# SCH_Camera-With-Light-Relay.net
KiCad netlist of a schematic drawn in EasyEDA
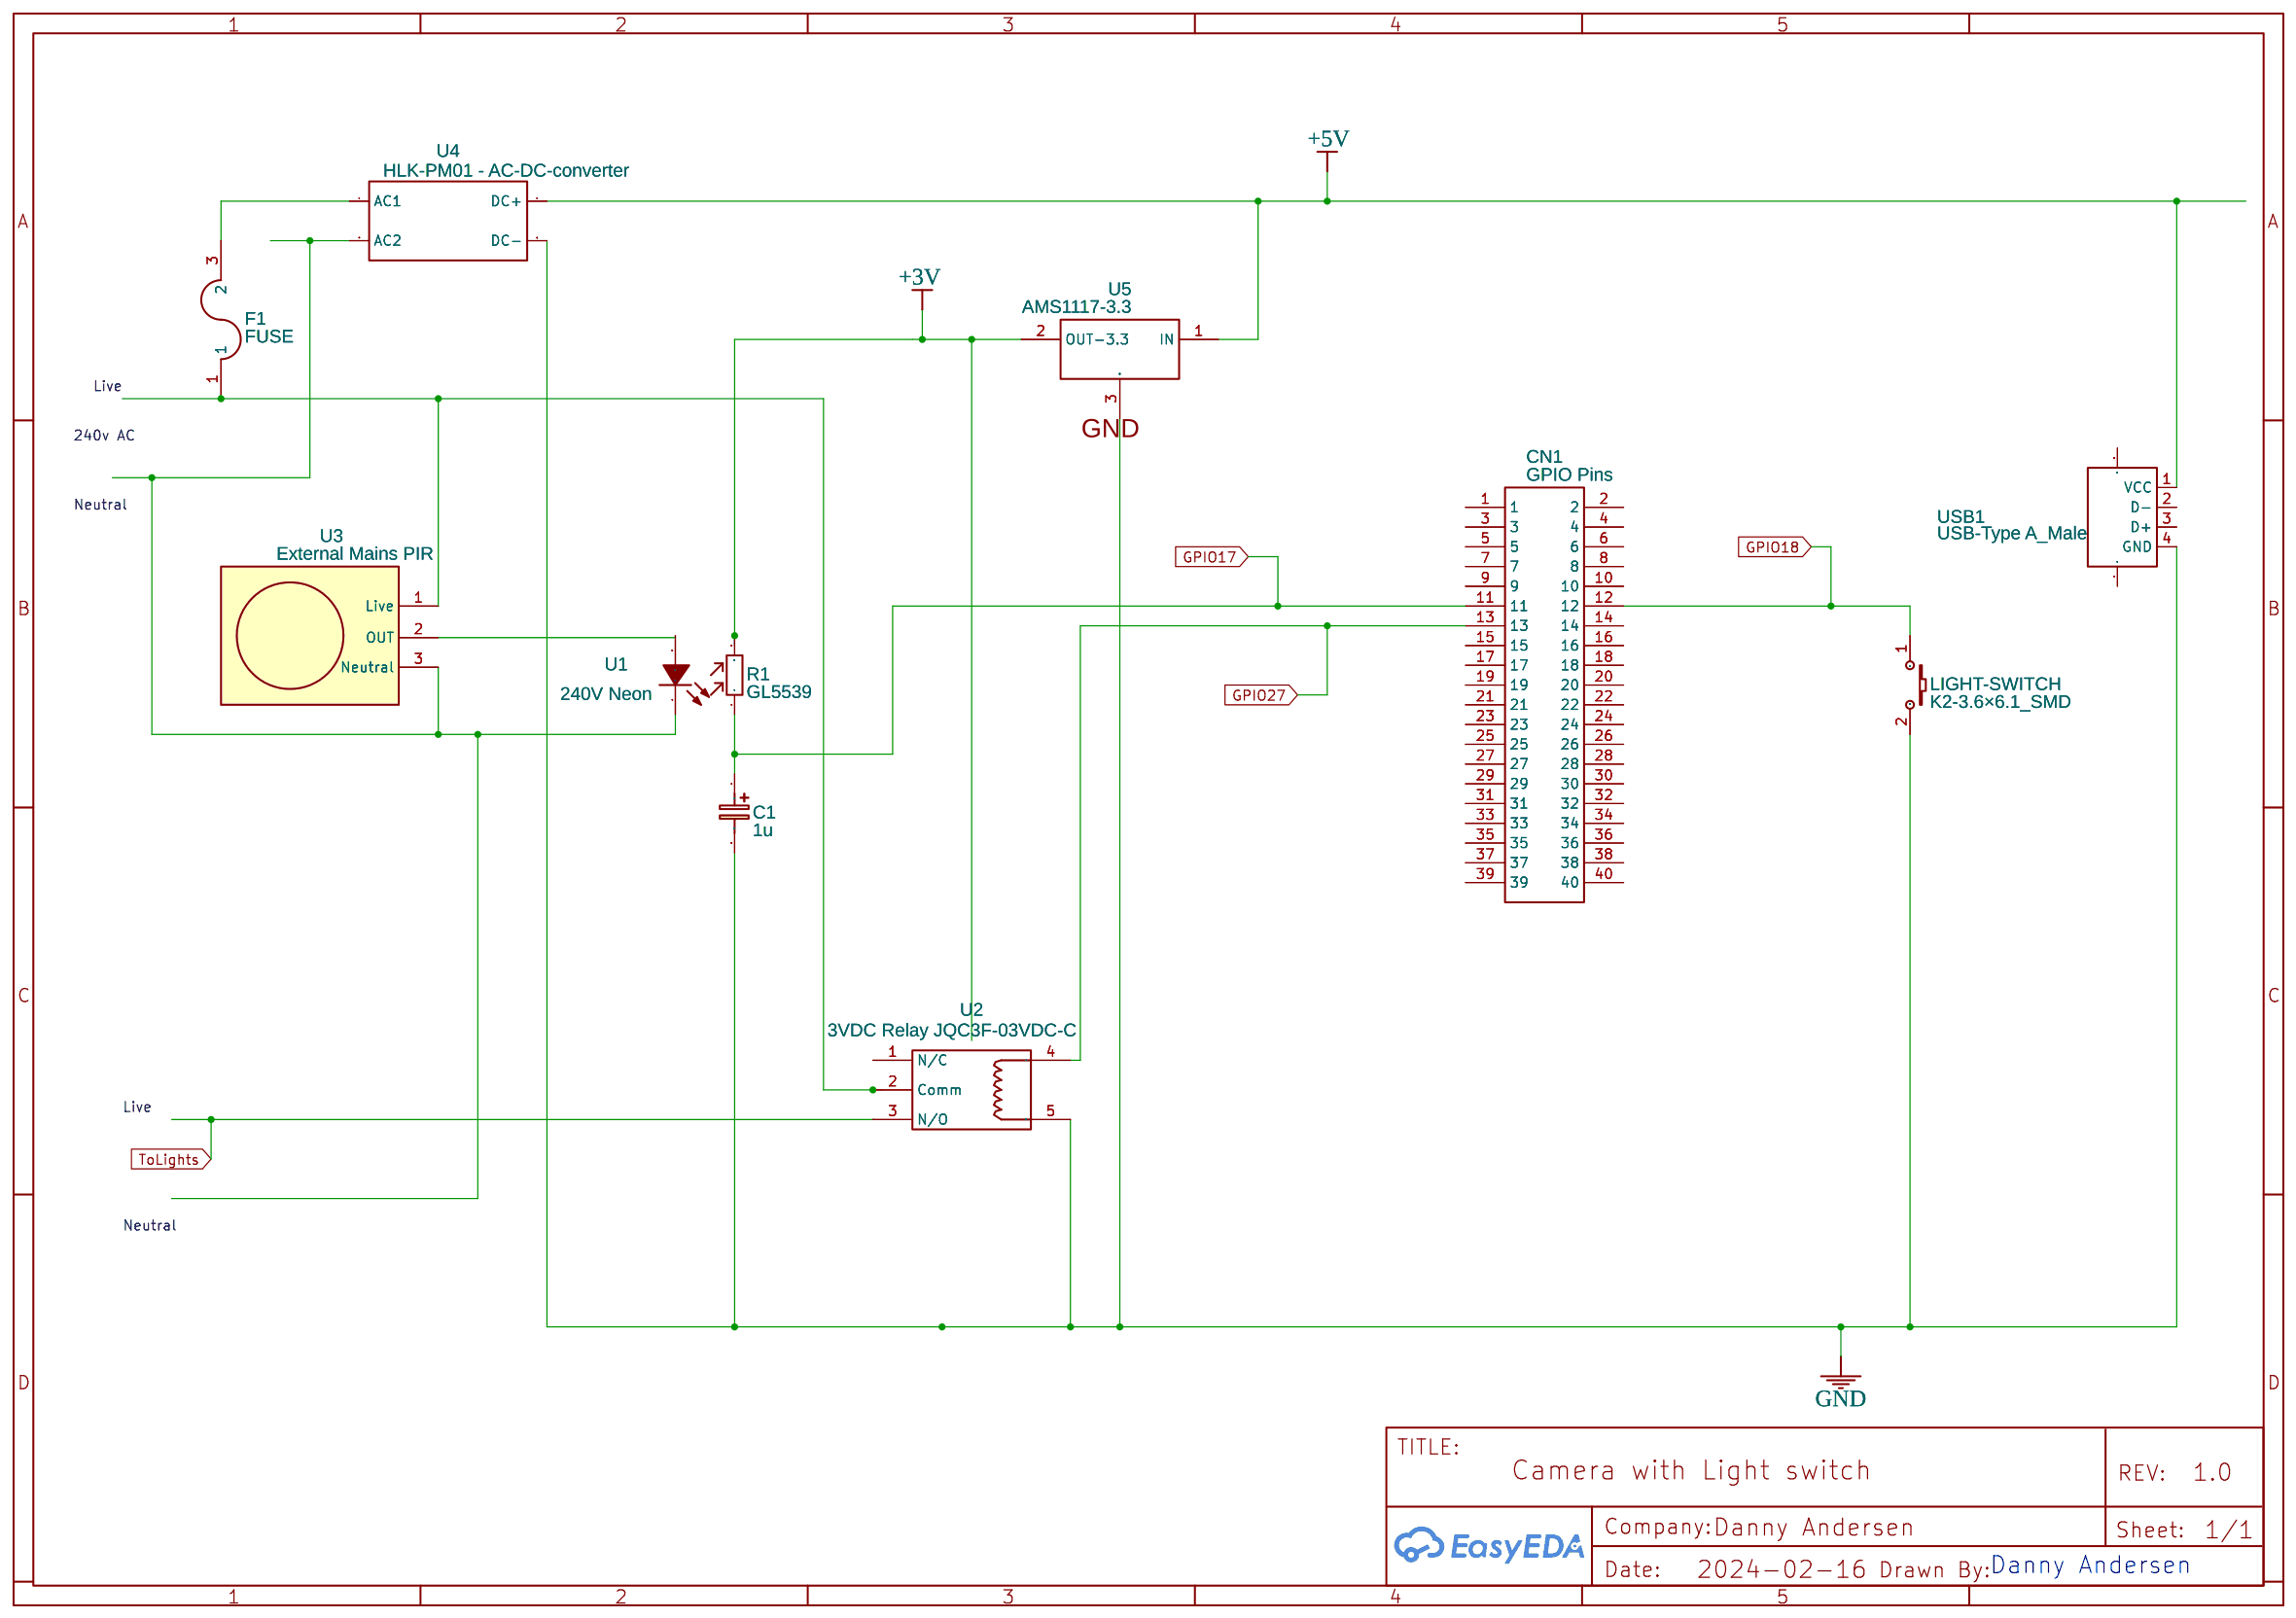
[diagram p0: schematic sheet]

(export (version "E")
  (design (tool "Eeschema 10.0.6"))
  (components
    (comp (ref "C1") (value "1u") (libsource (lib "") (part "C_Tan_SMD_A_EU")))
    (comp (ref "CN1")
      (value "GPIO Pins")
      (fields
        (field (name "Manufacturer Part") "2.54-2*20P压线头")
        (field (name "Manufacturer") "BOOMELE(博穆精密)")
      )
      (libsource (lib "") (part "Crimping terminals2*20"))
    )
    (comp (ref "F1")
      (value "FUSE")
      (fields (field (name "Manufacturer Part") "?"))
      (libsource (lib "") (part "Unknown_125_-1775"))
    )
    (comp (ref "LIGHT-SWITCH")
      (value "K2-3.6×6.1_SMD")
      (fields (field (name "Manufacturer Part") "K2-1107ST-A4SW-06"))
      (libsource (lib "") (part "K2-3.6×6.1_SMD"))
    )
    (comp (ref "R1")
      (value "GL5539")
      (fields (field (name "Manufacturer") "森霸"))
      (libsource (lib "") (part "GL5539"))
    )
    (comp (ref "U1")
      (value "240V Neon")
      (fields (field (name "Manufacturer Part") "720-LCGH9RNMXNX1"))
      (libsource (lib "") (part "720-LCGH9RNMXNX1"))
    )
    (comp (ref "U2")
      (value "3VDC Relay JQC3F-03VDC-C")
      (libsource (lib "") (part "3VDC Relay JQC3F-03VDC-C"))
    )
    (comp (ref "U3")
      (value "External Mains PIR")
      (fields (field (name "Manufacturer Part") "?"))
      (libsource (lib "") (part "Unknown_125_-1580"))
    )
    (comp (ref "U4")
      (value "HLK-PM01 - AC-DC-converter")
      (fields (field (name "Manufacturer Part") "?"))
      (libsource (lib "") (part "Unknown_230_-1825"))
    )
    (comp (ref "U5")
      (value "AMS1117-3.3")
      (fields (field (name "Manufacturer Part") "CJ78L05") (field (name "Manufacturer") "CJ"))
      (libsource (lib "") (part "7805(SOT-89)"))
    )
    (comp (ref "USB1")
      (value "USB-Type A_Male")
      (fields (field (name "Manufacturer Part") "USB-05") (field (name "Manufacturer") "SOFNG"))
      (libsource (lib "") (part "USB-Type A_Male"))
    )
  )
  (nets
    (net (code "1") (name "+3V") (class "Default")
      (node (ref "R1") (pin "2") (pinfunction "2_2") (pintype "input"))
      (node (ref "U5") (pin "2") (pinfunction "OUT-3.3_2") (pintype "passive"))
    )
    (net (code "2") (name "+5V") (class "Default")
      (node (ref "U4") (pin "4") (pinfunction "DC+_4") (pintype "unspecified"))
      (node (ref "U5") (pin "1") (pinfunction "IN_1") (pintype "passive"))
      (node (ref "USB1") (pin "1") (pinfunction "VCC_1") (pintype "input"))
    )
    (net (code "6") (name "GND") (class "Default")
      (node (ref "C1") (pin "2") (pinfunction "2_2") (pintype "unspecified"))
      (node (ref "LIGHT-SWITCH") (pin "2") (pinfunction "2_2") (pintype "unspecified"))
      (node (ref "U2") (pin "5") (pinfunction "5_5") (pintype "unspecified"))
      (node (ref "U4") (pin "3") (pinfunction "DC-_3") (pintype "unspecified"))
      (node (ref "U5") (pin "3") (pinfunction "GND_3") (pintype "passive"))
      (node (ref "USB1") (pin "4") (pinfunction "GND_4") (pintype "input"))
    )
    (net (code "7") (name "GPIO17") (class "Default")
      (node (ref "C1") (pin "1") (pinfunction "1_1") (pintype "unspecified"))
      (node (ref "CN1") (pin "11") (pinfunction "11_11") (pintype "unspecified"))
      (node (ref "R1") (pin "1") (pinfunction "1_1") (pintype "input"))
    )
    (net (code "8") (name "GPIO18") (class "Default")
      (node (ref "CN1") (pin "12") (pinfunction "12_12") (pintype "unspecified"))
      (node (ref "LIGHT-SWITCH") (pin "1") (pinfunction "1_1") (pintype "unspecified"))
    )
    (net (code "9") (name "GPIO27") (class "Default")
      (node (ref "CN1") (pin "13") (pinfunction "13_13") (pintype "unspecified"))
      (node (ref "U2") (pin "4") (pinfunction "4_4") (pintype "unspecified"))
    )
    (net (code "10") (name "Net-(F1-2)") (class "Default")
      (node (ref "F1") (pin "3") (pinfunction "2_3") (pintype "unspecified"))
      (node (ref "U4") (pin "1") (pinfunction "AC1_1") (pintype "input"))
    )
    (net (code "11") (name "Net-(U1-A)") (class "Default")
      (node (ref "U1") (pin "2") (pinfunction "A_2") (pintype "unspecified"))
      (node (ref "U3") (pin "2") (pinfunction "OUT_2") (pintype "unspecified"))
    )
    (net (code "12") (name "Net-(U1-K)") (class "Default")
      (node (ref "U1") (pin "1") (pinfunction "K_1") (pintype "unspecified"))
      (node (ref "U3") (pin "3") (pinfunction "Neutral_3") (pintype "unspecified"))
      (node (ref "U4") (pin "2") (pinfunction "AC2_2") (pintype "input"))
    )
    (net (code "13") (name "Net-(U2-Comm)") (class "Default")
      (node (ref "F1") (pin "1") (pinfunction "1_1") (pintype "unspecified"))
      (node (ref "U2") (pin "2") (pinfunction "Comm_2") (pintype "unspecified"))
      (node (ref "U3") (pin "1") (pinfunction "Live_1") (pintype "unspecified"))
    )
    (net (code "14") (name "ToLights") (class "Default")
      (node (ref "U2") (pin "3") (pinfunction "N/O_3") (pintype "unspecified"))
    )
    (net (code "15") (name "unconnected-(CN1-Pad1)") (class "Default")
      (node (ref "CN1") (pin "1") (pinfunction "1_1") (pintype "unspecified"))
    )
    (net (code "16") (name "unconnected-(CN1-Pad2)") (class "Default")
      (node (ref "CN1") (pin "2") (pinfunction "2_2") (pintype "unspecified"))
    )
    (net (code "17") (name "unconnected-(CN1-Pad3)") (class "Default")
      (node (ref "CN1") (pin "3") (pinfunction "3_3") (pintype "unspecified"))
    )
    (net (code "18") (name "unconnected-(CN1-Pad4)") (class "Default")
      (node (ref "CN1") (pin "4") (pinfunction "4_4") (pintype "unspecified"))
    )
    (net (code "19") (name "unconnected-(CN1-Pad5)") (class "Default")
      (node (ref "CN1") (pin "5") (pinfunction "5_5") (pintype "unspecified"))
    )
    (net (code "20") (name "unconnected-(CN1-Pad6)") (class "Default")
      (node (ref "CN1") (pin "6") (pinfunction "6_6") (pintype "unspecified"))
    )
    (net (code "21") (name "unconnected-(CN1-Pad7)") (class "Default")
      (node (ref "CN1") (pin "7") (pinfunction "7_7") (pintype "unspecified"))
    )
    (net (code "22") (name "unconnected-(CN1-Pad8)") (class "Default")
      (node (ref "CN1") (pin "8") (pinfunction "8_8") (pintype "unspecified"))
    )
    (net (code "23") (name "unconnected-(CN1-Pad9)") (class "Default")
      (node (ref "CN1") (pin "9") (pinfunction "9_9") (pintype "unspecified"))
    )
    (net (code "24") (name "unconnected-(CN1-Pad10)") (class "Default")
      (node (ref "CN1") (pin "10") (pinfunction "10_10") (pintype "unspecified"))
    )
    (net (code "25") (name "unconnected-(CN1-Pad14)") (class "Default")
      (node (ref "CN1") (pin "14") (pinfunction "14_14") (pintype "unspecified"))
    )
    (net (code "26") (name "unconnected-(CN1-Pad15)") (class "Default")
      (node (ref "CN1") (pin "15") (pinfunction "15_15") (pintype "unspecified"))
    )
    (net (code "27") (name "unconnected-(CN1-Pad16)") (class "Default")
      (node (ref "CN1") (pin "16") (pinfunction "16_16") (pintype "unspecified"))
    )
    (net (code "28") (name "unconnected-(CN1-Pad17)") (class "Default")
      (node (ref "CN1") (pin "17") (pinfunction "17_17") (pintype "unspecified"))
    )
    (net (code "29") (name "unconnected-(CN1-Pad18)") (class "Default")
      (node (ref "CN1") (pin "18") (pinfunction "18_18") (pintype "unspecified"))
    )
    (net (code "30") (name "unconnected-(CN1-Pad19)") (class "Default")
      (node (ref "CN1") (pin "19") (pinfunction "19_19") (pintype "unspecified"))
    )
    (net (code "31") (name "unconnected-(CN1-Pad20)") (class "Default")
      (node (ref "CN1") (pin "20") (pinfunction "20_20") (pintype "unspecified"))
    )
    (net (code "32") (name "unconnected-(CN1-Pad21)") (class "Default")
      (node (ref "CN1") (pin "21") (pinfunction "21_21") (pintype "unspecified"))
    )
    (net (code "33") (name "unconnected-(CN1-Pad22)") (class "Default")
      (node (ref "CN1") (pin "22") (pinfunction "22_22") (pintype "unspecified"))
    )
    (net (code "34") (name "unconnected-(CN1-Pad23)") (class "Default")
      (node (ref "CN1") (pin "23") (pinfunction "23_23") (pintype "unspecified"))
    )
    (net (code "35") (name "unconnected-(CN1-Pad24)") (class "Default")
      (node (ref "CN1") (pin "24") (pinfunction "24_24") (pintype "unspecified"))
    )
    (net (code "36") (name "unconnected-(CN1-Pad25)") (class "Default")
      (node (ref "CN1") (pin "25") (pinfunction "25_25") (pintype "unspecified"))
    )
    (net (code "37") (name "unconnected-(CN1-Pad26)") (class "Default")
      (node (ref "CN1") (pin "26") (pinfunction "26_26") (pintype "unspecified"))
    )
    (net (code "38") (name "unconnected-(CN1-Pad27)") (class "Default")
      (node (ref "CN1") (pin "27") (pinfunction "27_27") (pintype "unspecified"))
    )
    (net (code "39") (name "unconnected-(CN1-Pad28)") (class "Default")
      (node (ref "CN1") (pin "28") (pinfunction "28_28") (pintype "unspecified"))
    )
    (net (code "40") (name "unconnected-(CN1-Pad29)") (class "Default")
      (node (ref "CN1") (pin "29") (pinfunction "29_29") (pintype "unspecified"))
    )
    (net (code "41") (name "unconnected-(CN1-Pad30)") (class "Default")
      (node (ref "CN1") (pin "30") (pinfunction "30_30") (pintype "unspecified"))
    )
    (net (code "42") (name "unconnected-(CN1-Pad31)") (class "Default")
      (node (ref "CN1") (pin "31") (pinfunction "31_31") (pintype "unspecified"))
    )
    (net (code "43") (name "unconnected-(CN1-Pad32)") (class "Default")
      (node (ref "CN1") (pin "32") (pinfunction "32_32") (pintype "unspecified"))
    )
    (net (code "44") (name "unconnected-(CN1-Pad33)") (class "Default")
      (node (ref "CN1") (pin "33") (pinfunction "33_33") (pintype "unspecified"))
    )
    (net (code "45") (name "unconnected-(CN1-Pad34)") (class "Default")
      (node (ref "CN1") (pin "34") (pinfunction "34_34") (pintype "unspecified"))
    )
    (net (code "46") (name "unconnected-(CN1-Pad35)") (class "Default")
      (node (ref "CN1") (pin "35") (pinfunction "35_35") (pintype "unspecified"))
    )
    (net (code "47") (name "unconnected-(CN1-Pad36)") (class "Default")
      (node (ref "CN1") (pin "36") (pinfunction "36_36") (pintype "unspecified"))
    )
    (net (code "48") (name "unconnected-(CN1-Pad37)") (class "Default")
      (node (ref "CN1") (pin "37") (pinfunction "37_37") (pintype "unspecified"))
    )
    (net (code "49") (name "unconnected-(CN1-Pad38)") (class "Default")
      (node (ref "CN1") (pin "38") (pinfunction "38_38") (pintype "unspecified"))
    )
    (net (code "50") (name "unconnected-(CN1-Pad39)") (class "Default")
      (node (ref "CN1") (pin "39") (pinfunction "39_39") (pintype "unspecified"))
    )
    (net (code "51") (name "unconnected-(CN1-Pad40)") (class "Default")
      (node (ref "CN1") (pin "40") (pinfunction "40_40") (pintype "unspecified"))
    )
    (net (code "52") (name "unconnected-(U2-N{slash}C-Pad1)") (class "Default")
      (node (ref "U2") (pin "1") (pinfunction "N/C_1") (pintype "unspecified"))
    )
    (net (code "53") (name "unconnected-(USB1-D+-Pad3)") (class "Default")
      (node (ref "USB1") (pin "3") (pinfunction "D+_3") (pintype "input"))
    )
    (net (code "54") (name "unconnected-(USB1-D--Pad2)") (class "Default")
      (node (ref "USB1") (pin "2") (pinfunction "D-_2") (pintype "input"))
    )
    (net (code "55") (name "unconnected-(USB1-Pad5)") (class "Default")
      (node (ref "USB1") (pin "5") (pinfunction "5_5") (pintype "unspecified"))
    )
    (net (code "56") (name "unconnected-(USB1-Pad6)") (class "Default")
      (node (ref "USB1") (pin "6") (pinfunction "6_6") (pintype "unspecified"))
    )
  )
)
